# MdA_RS485.net
KiCad netlist of a schematic drawn in Altium Designer
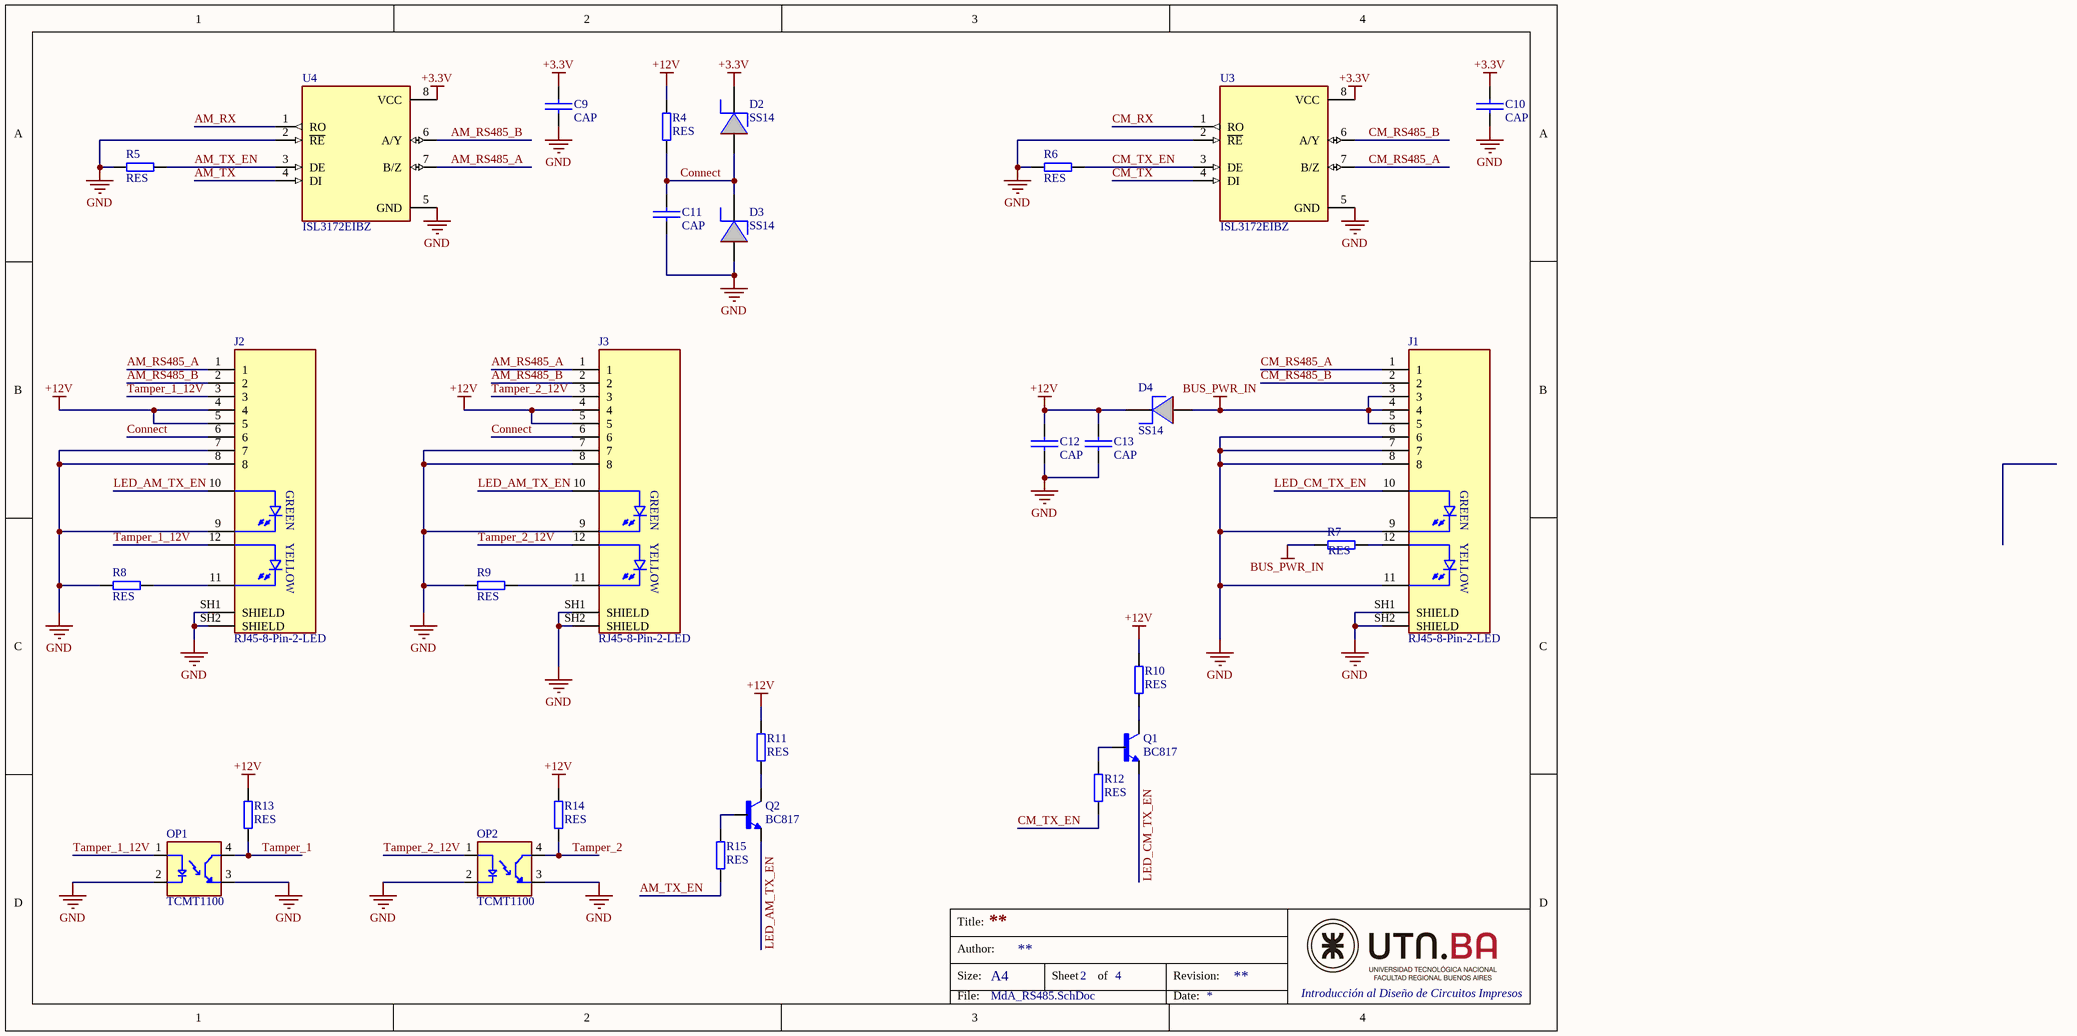
[diagram p0: MdA_RS485.SchDoc]

(export (version "E")
  (design (tool "Eeschema 10.0.6"))
  (components
    (comp (ref "C9") (value "CAP") (footprint "C_0402") (libsource (lib "Modulo de apertura") (part "CAP")))
    (comp (ref "C10") (value "CAP") (footprint "C_0402") (libsource (lib "Modulo de apertura") (part "CAP")))
    (comp (ref "C11") (value "CAP") (footprint "C_0402") (libsource (lib "Modulo de apertura") (part "CAP")))
    (comp (ref "C12") (value "CAP") (footprint "C_0402") (libsource (lib "Modulo de apertura") (part "CAP")))
    (comp (ref "C13") (value "CAP") (footprint "C_0603") (libsource (lib "Modulo de apertura") (part "CAP")))
    (comp (ref "D2")
      (value "SS14")
      (footprint "D_SMA")
      (libsource (lib "Modulo de apertura") (part "DIODE_SH"))
    )
    (comp (ref "D3")
      (value "SS14")
      (footprint "D_SMA")
      (libsource (lib "Modulo de apertura") (part "DIODE_SH"))
    )
    (comp (ref "D4")
      (value "SS14")
      (footprint "D_SMA")
      (libsource (lib "Modulo de apertura") (part "DIODE_SH"))
    )
    (comp (ref "J1")
      (value "RJ45-8-Pin-2-LED")
      (footprint "RJ45-8-Pin-2-Led")
      (libsource (lib "Modulo de apertura") (part "RJ45-8-Pin-2-LED"))
    )
    (comp (ref "J2")
      (value "RJ45-8-Pin-2-LED")
      (footprint "RJ45-8-Pin-2-Led")
      (libsource (lib "Modulo de apertura") (part "RJ45-8-Pin-2-LED"))
    )
    (comp (ref "J3")
      (value "RJ45-8-Pin-2-LED")
      (footprint "RJ45-8-Pin-2-Led")
      (libsource (lib "Modulo de apertura") (part "RJ45-8-Pin-2-LED"))
    )
    (comp (ref "OP1")
      (value "TCMT1100")
      (footprint "SSOP4")
      (libsource (lib "Modulo de apertura") (part "TCMT1100"))
    )
    (comp (ref "OP2")
      (value "TCMT1100")
      (footprint "SSOP4")
      (libsource (lib "Modulo de apertura") (part "TCMT1100"))
    )
    (comp (ref "Q1")
      (value "BC817")
      (footprint "SOT-23-3")
      (libsource (lib "Modulo de apertura") (part "BC817"))
    )
    (comp (ref "Q2")
      (value "BC817")
      (footprint "SOT-23-3")
      (libsource (lib "Modulo de apertura") (part "BC817"))
    )
    (comp (ref "R4") (value "RES") (footprint "R_0402") (libsource (lib "Modulo de apertura") (part "RES")))
    (comp (ref "R5") (value "RES") (footprint "R_0402") (libsource (lib "Modulo de apertura") (part "RES")))
    (comp (ref "R6") (value "RES") (footprint "R_0402") (libsource (lib "Modulo de apertura") (part "RES")))
    (comp (ref "R7") (value "RES") (footprint "R_0402") (libsource (lib "Modulo de apertura") (part "RES")))
    (comp (ref "R8") (value "RES") (footprint "R_0402") (libsource (lib "Modulo de apertura") (part "RES")))
    (comp (ref "R9") (value "RES") (footprint "R_0402") (libsource (lib "Modulo de apertura") (part "RES")))
    (comp (ref "R10") (value "RES") (footprint "R_0402") (libsource (lib "Modulo de apertura") (part "RES")))
    (comp (ref "R11") (value "RES") (footprint "R_0402") (libsource (lib "Modulo de apertura") (part "RES")))
    (comp (ref "R12") (value "RES") (footprint "R_0402") (libsource (lib "Modulo de apertura") (part "RES")))
    (comp (ref "R13") (value "RES") (footprint "R_0402") (libsource (lib "Modulo de apertura") (part "RES")))
    (comp (ref "R14") (value "RES") (footprint "R_0402") (libsource (lib "Modulo de apertura") (part "RES")))
    (comp (ref "R15") (value "RES") (footprint "R_0402") (libsource (lib "Modulo de apertura") (part "RES")))
    (comp (ref "U3")
      (value "ISL3172EIBZ")
      (footprint "SOIC-8")
      (description "Transceiver Half RS422, RS485 8-SOIC")
      (libsource (lib "Modulo de apertura") (part "ISL3172EIBZ"))
    )
    (comp (ref "U4")
      (value "ISL3172EIBZ")
      (footprint "SOIC-8")
      (description "Transceiver Half RS422, RS485 8-SOIC")
      (libsource (lib "Modulo de apertura") (part "ISL3172EIBZ"))
    )
  )
  (nets
    (net (code "1") (name "+3.3V") (class "Default")
      (node (ref "C10") (pin "1") (pinfunction "1_1") (pintype "passive"))
      (node (ref "C9") (pin "1") (pinfunction "1_1") (pintype "passive"))
      (node (ref "D2") (pin "2") (pinfunction "K_2") (pintype "passive"))
      (node (ref "U3") (pin "8") (pinfunction "VCC_8") (pintype "power_in"))
      (node (ref "U4") (pin "8") (pinfunction "VCC_8") (pintype "power_in"))
    )
    (net (code "2") (name "+12V") (class "Default")
      (node (ref "C12") (pin "1") (pinfunction "1_1") (pintype "passive"))
      (node (ref "C13") (pin "1") (pinfunction "1_1") (pintype "passive"))
      (node (ref "D4") (pin "2") (pinfunction "K_2") (pintype "passive"))
      (node (ref "J2") (pin "4") (pinfunction "4_4") (pintype "passive"))
      (node (ref "J2") (pin "5") (pinfunction "5_5") (pintype "passive"))
      (node (ref "J3") (pin "4") (pinfunction "4_4") (pintype "passive"))
      (node (ref "J3") (pin "5") (pinfunction "5_5") (pintype "passive"))
      (node (ref "R10") (pin "1") (pinfunction "1_1") (pintype "passive"))
      (node (ref "R11") (pin "1") (pinfunction "1_1") (pintype "passive"))
      (node (ref "R13") (pin "1") (pinfunction "1_1") (pintype "passive"))
      (node (ref "R14") (pin "1") (pinfunction "1_1") (pintype "passive"))
      (node (ref "R4") (pin "1") (pinfunction "1_1") (pintype "passive"))
    )
    (net (code "3") (name "/AM_RS485_A") (class "Default")
      (node (ref "J2") (pin "1") (pinfunction "1_1") (pintype "passive"))
      (node (ref "J3") (pin "1") (pinfunction "1_1") (pintype "passive"))
      (node (ref "U4") (pin "7") (pinfunction "B/Z_7") (pintype "bidirectional"))
    )
    (net (code "4") (name "/AM_RS485_B") (class "Default")
      (node (ref "J2") (pin "2") (pinfunction "2_2") (pintype "passive"))
      (node (ref "J3") (pin "2") (pinfunction "2_2") (pintype "passive"))
      (node (ref "U4") (pin "6") (pinfunction "A/Y_6") (pintype "bidirectional"))
    )
    (net (code "5") (name "/AM_RX") (class "Default")
      (node (ref "U4") (pin "1") (pinfunction "RO_1") (pintype "output"))
    )
    (net (code "6") (name "/AM_TX") (class "Default")
      (node (ref "U4") (pin "4") (pinfunction "DI_4") (pintype "input"))
    )
    (net (code "7") (name "/AM_TX_EN") (class "Default")
      (node (ref "R15") (pin "2") (pinfunction "2_2") (pintype "passive"))
      (node (ref "R5") (pin "1") (pinfunction "1_1") (pintype "passive"))
      (node (ref "U4") (pin "3") (pinfunction "DE_3") (pintype "input"))
    )
    (net (code "8") (name "/CM_RS485_A") (class "Default")
      (node (ref "J1") (pin "1") (pinfunction "1_1") (pintype "passive"))
      (node (ref "U3") (pin "7") (pinfunction "B/Z_7") (pintype "bidirectional"))
    )
    (net (code "9") (name "/CM_RS485_B") (class "Default")
      (node (ref "J1") (pin "2") (pinfunction "2_2") (pintype "passive"))
      (node (ref "U3") (pin "6") (pinfunction "A/Y_6") (pintype "bidirectional"))
    )
    (net (code "10") (name "/CM_RX") (class "Default")
      (node (ref "U3") (pin "1") (pinfunction "RO_1") (pintype "output"))
    )
    (net (code "11") (name "/CM_TX") (class "Default")
      (node (ref "U3") (pin "4") (pinfunction "DI_4") (pintype "input"))
    )
    (net (code "12") (name "/CM_TX_EN") (class "Default")
      (node (ref "R12") (pin "2") (pinfunction "2_2") (pintype "passive"))
      (node (ref "R6") (pin "1") (pinfunction "1_1") (pintype "passive"))
      (node (ref "U3") (pin "3") (pinfunction "DE_3") (pintype "input"))
    )
    (net (code "13") (name "/Connect") (class "Default")
      (node (ref "C11") (pin "1") (pinfunction "1_1") (pintype "passive"))
      (node (ref "D2") (pin "1") (pinfunction "A_1") (pintype "passive"))
      (node (ref "D3") (pin "2") (pinfunction "K_2") (pintype "passive"))
      (node (ref "J2") (pin "6") (pinfunction "6_6") (pintype "passive"))
      (node (ref "J3") (pin "6") (pinfunction "6_6") (pintype "passive"))
      (node (ref "R4") (pin "2") (pinfunction "2_2") (pintype "passive"))
    )
    (net (code "14") (name "/LED_AM_TX_EN") (class "Default")
      (node (ref "J2") (pin "10") (pinfunction "10_10") (pintype "passive"))
      (node (ref "J3") (pin "10") (pinfunction "10_10") (pintype "passive"))
      (node (ref "Q2") (pin "2") (pinfunction "E_2") (pintype "passive"))
    )
    (net (code "15") (name "/LED_CM_TX_EN") (class "Default")
      (node (ref "J1") (pin "10") (pinfunction "10_10") (pintype "passive"))
      (node (ref "Q1") (pin "2") (pinfunction "E_2") (pintype "passive"))
    )
    (net (code "16") (name "/Tamper_1") (class "Default")
      (node (ref "OP1") (pin "4") (pinfunction "CT_4") (pintype "passive"))
      (node (ref "R13") (pin "2") (pinfunction "2_2") (pintype "passive"))
    )
    (net (code "17") (name "/Tamper_1_12V") (class "Default")
      (node (ref "J2") (pin "12") (pinfunction "12_12") (pintype "passive"))
      (node (ref "J2") (pin "3") (pinfunction "3_3") (pintype "passive"))
      (node (ref "OP1") (pin "1") (pinfunction "A_1") (pintype "passive"))
    )
    (net (code "18") (name "/Tamper_2") (class "Default")
      (node (ref "OP2") (pin "4") (pinfunction "CT_4") (pintype "passive"))
      (node (ref "R14") (pin "2") (pinfunction "2_2") (pintype "passive"))
    )
    (net (code "19") (name "/Tamper_2_12V") (class "Default")
      (node (ref "J3") (pin "12") (pinfunction "12_12") (pintype "passive"))
      (node (ref "J3") (pin "3") (pinfunction "3_3") (pintype "passive"))
      (node (ref "OP2") (pin "1") (pinfunction "A_1") (pintype "passive"))
    )
    (net (code "20") (name "BUS_PWR_IN") (class "Default")
      (node (ref "D4") (pin "1") (pinfunction "A_1") (pintype "passive"))
      (node (ref "J1") (pin "3") (pinfunction "3_3") (pintype "passive"))
      (node (ref "J1") (pin "4") (pinfunction "4_4") (pintype "passive"))
      (node (ref "J1") (pin "5") (pinfunction "5_5") (pintype "passive"))
      (node (ref "R7") (pin "2") (pinfunction "2_2") (pintype "passive"))
    )
    (net (code "21") (name "GND") (class "Default")
      (node (ref "C10") (pin "2") (pinfunction "2_2") (pintype "passive"))
      (node (ref "C11") (pin "2") (pinfunction "2_2") (pintype "passive"))
      (node (ref "C12") (pin "2") (pinfunction "2_2") (pintype "passive"))
      (node (ref "C13") (pin "2") (pinfunction "2_2") (pintype "passive"))
      (node (ref "C9") (pin "2") (pinfunction "2_2") (pintype "passive"))
      (node (ref "D3") (pin "1") (pinfunction "A_1") (pintype "passive"))
      (node (ref "J1") (pin "11") (pinfunction "11_11") (pintype "passive"))
      (node (ref "J1") (pin "6") (pinfunction "6_6") (pintype "passive"))
      (node (ref "J1") (pin "7") (pinfunction "7_7") (pintype "passive"))
      (node (ref "J1") (pin "8") (pinfunction "8_8") (pintype "passive"))
      (node (ref "J1") (pin "9") (pinfunction "9_9") (pintype "passive"))
      (node (ref "J1") (pin "SH1") (pinfunction "SHIELD_SH1") (pintype "passive"))
      (node (ref "J1") (pin "SH2") (pinfunction "SHIELD_SH2") (pintype "passive"))
      (node (ref "J2") (pin "7") (pinfunction "7_7") (pintype "passive"))
      (node (ref "J2") (pin "8") (pinfunction "8_8") (pintype "passive"))
      (node (ref "J2") (pin "9") (pinfunction "9_9") (pintype "passive"))
      (node (ref "J2") (pin "SH1") (pinfunction "SHIELD_SH1") (pintype "passive"))
      (node (ref "J2") (pin "SH2") (pinfunction "SHIELD_SH2") (pintype "passive"))
      (node (ref "J3") (pin "7") (pinfunction "7_7") (pintype "passive"))
      (node (ref "J3") (pin "8") (pinfunction "8_8") (pintype "passive"))
      (node (ref "J3") (pin "9") (pinfunction "9_9") (pintype "passive"))
      (node (ref "J3") (pin "SH1") (pinfunction "SHIELD_SH1") (pintype "passive"))
      (node (ref "J3") (pin "SH2") (pinfunction "SHIELD_SH2") (pintype "passive"))
      (node (ref "OP1") (pin "2") (pinfunction "C_2") (pintype "passive"))
      (node (ref "OP1") (pin "3") (pinfunction "ET_3") (pintype "passive"))
      (node (ref "OP2") (pin "2") (pinfunction "C_2") (pintype "passive"))
      (node (ref "OP2") (pin "3") (pinfunction "ET_3") (pintype "passive"))
      (node (ref "R5") (pin "2") (pinfunction "2_2") (pintype "passive"))
      (node (ref "R6") (pin "2") (pinfunction "2_2") (pintype "passive"))
      (node (ref "R8") (pin "2") (pinfunction "2_2") (pintype "passive"))
      (node (ref "R9") (pin "2") (pinfunction "2_2") (pintype "passive"))
      (node (ref "U3") (pin "2") (pinfunction "~{RE}_2") (pintype "input"))
      (node (ref "U3") (pin "5") (pinfunction "GND_5") (pintype "power_in"))
      (node (ref "U4") (pin "2") (pinfunction "~{RE}_2") (pintype "input"))
      (node (ref "U4") (pin "5") (pinfunction "GND_5") (pintype "power_in"))
    )
    (net (code "22") (name "Net-(J1-Pad12)") (class "Default")
      (node (ref "J1") (pin "12") (pinfunction "12_12") (pintype "passive"))
      (node (ref "R7") (pin "1") (pinfunction "1_1") (pintype "passive"))
    )
    (net (code "23") (name "Net-(J2-Pad11)") (class "Default")
      (node (ref "J2") (pin "11") (pinfunction "11_11") (pintype "passive"))
      (node (ref "R8") (pin "1") (pinfunction "1_1") (pintype "passive"))
    )
    (net (code "24") (name "Net-(J3-Pad11)") (class "Default")
      (node (ref "J3") (pin "11") (pinfunction "11_11") (pintype "passive"))
      (node (ref "R9") (pin "1") (pinfunction "1_1") (pintype "passive"))
    )
    (net (code "25") (name "Net-(Q1-B)") (class "Default")
      (node (ref "Q1") (pin "1") (pinfunction "B_1") (pintype "passive"))
      (node (ref "R12") (pin "1") (pinfunction "1_1") (pintype "passive"))
    )
    (net (code "26") (name "Net-(Q1-C)") (class "Default")
      (node (ref "Q1") (pin "3") (pinfunction "C_3") (pintype "passive"))
      (node (ref "R10") (pin "2") (pinfunction "2_2") (pintype "passive"))
    )
    (net (code "27") (name "Net-(Q2-B)") (class "Default")
      (node (ref "Q2") (pin "1") (pinfunction "B_1") (pintype "passive"))
      (node (ref "R15") (pin "1") (pinfunction "1_1") (pintype "passive"))
    )
    (net (code "28") (name "Net-(Q2-C)") (class "Default")
      (node (ref "Q2") (pin "3") (pinfunction "C_3") (pintype "passive"))
      (node (ref "R11") (pin "2") (pinfunction "2_2") (pintype "passive"))
    )
  )
)
